# CenterBoard_Mega16.net
KiCad netlist of a schematic drawn in Altium Designer
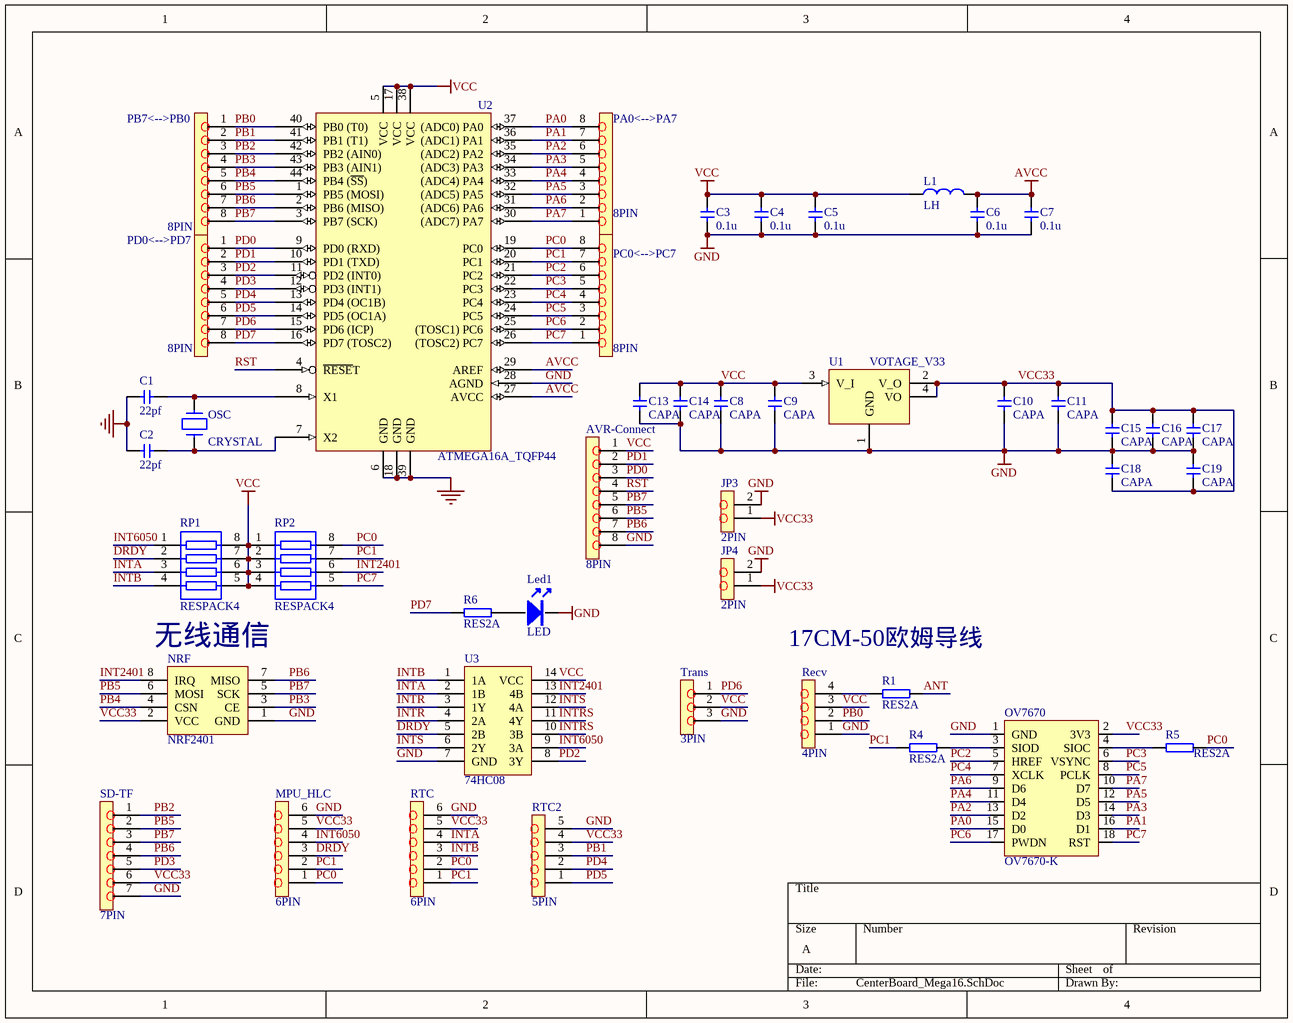
[diagram p0: CenterBoard_Mega16.SchDoc]

(export (version "E")
  (design (tool "Eeschema 10.0.6"))
  (components
    (comp (ref "AVR-Connect") (value "8PIN") (footprint "SIP8") (libsource (lib "") (part "8PIN_1")))
    (comp (ref "C1") (value "22pf") (footprint "RC100") (libsource (lib "Common") (part "CAPA")))
    (comp (ref "C2") (value "22pf") (footprint "RC100") (libsource (lib "Common") (part "CAPA")))
    (comp (ref "C3") (value "0.1u") (footprint "RC100") (libsource (lib "Common") (part "CAPA")))
    (comp (ref "C4") (value "0.1u") (footprint "RC100") (libsource (lib "Common") (part "CAPA")))
    (comp (ref "C5") (value "0.1u") (footprint "RC100") (libsource (lib "Common") (part "CAPA")))
    (comp (ref "C6") (value "0.1u") (footprint "RC100") (libsource (lib "Common") (part "CAPA")))
    (comp (ref "C7") (value "0.1u") (footprint "RC100") (libsource (lib "Common") (part "CAPA")))
    (comp (ref "C8") (value "CAPA") (footprint "RC100") (libsource (lib "Common") (part "CAPA")))
    (comp (ref "C9") (value "CAPA") (footprint "RC100") (libsource (lib "Common") (part "CAPA")))
    (comp (ref "C10") (value "CAPA") (footprint "RC100") (libsource (lib "Common") (part "CAPA")))
    (comp (ref "C11") (value "CAPA") (footprint "RC100") (libsource (lib "Common") (part "CAPA")))
    (comp (ref "C13") (value "CAPA") (footprint "RC100") (libsource (lib "Common") (part "CAPA")))
    (comp (ref "C14") (value "CAPA") (footprint "RC100") (libsource (lib "Common") (part "CAPA")))
    (comp (ref "C15") (value "CAPA") (footprint "RC100") (libsource (lib "Common") (part "CAPA")))
    (comp (ref "C16") (value "CAPA") (footprint "RC100") (libsource (lib "Common") (part "CAPA")))
    (comp (ref "C17") (value "CAPA") (footprint "RC100") (libsource (lib "Common") (part "CAPA")))
    (comp (ref "C18") (value "CAPA") (footprint "RC100") (libsource (lib "Common") (part "CAPA")))
    (comp (ref "C19") (value "CAPA") (footprint "RC100") (libsource (lib "Common") (part "CAPA")))
    (comp (ref "JP3") (value "2PIN") (footprint "SIP2") (libsource (lib "Common") (part "2PIN")))
    (comp (ref "JP4") (value "2PIN") (footprint "SIP2") (libsource (lib "Common") (part "2PIN")))
    (comp (ref "L1") (value "LH") (footprint "1206") (libsource (lib "Common") (part "LH")))
    (comp (ref "Led1") (value "LED") (footprint "LED") (libsource (lib "Common") (part "LED")))
    (comp (ref "MPU_HLC") (value "6PIN") (footprint "SIP6") (libsource (lib "Common") (part "6PIN")))
    (comp (ref "NRF") (value "NRF2401") (footprint "NRF2401") (libsource (lib "Common") (part "NRF2401")))
    (comp (ref "OSC") (value "CRYSTAL") (footprint "OSC200") (libsource (lib "Common") (part "CRYSTAL")))
    (comp (ref "OV7670") (value "OV7670-K") (footprint "SIP9X2") (libsource (lib "Common") (part "OV7670-K")))
    (comp (ref "PA0<-->PA7") (value "8PIN") (footprint "SIP8") (libsource (lib "Common") (part "8PIN")))
    (comp (ref "PB7<-->PB0") (value "8PIN") (footprint "SIP8") (libsource (lib "") (part "8PIN_1")))
    (comp (ref "PC0<-->PC7") (value "8PIN") (footprint "SIP8") (libsource (lib "Common") (part "8PIN")))
    (comp (ref "PD0<-->PD7") (value "8PIN") (footprint "SIP8") (libsource (lib "") (part "8PIN_1")))
    (comp (ref "R1") (value "RES2A") (footprint "0805") (libsource (lib "Common") (part "RES2A")))
    (comp (ref "R4") (value "RES2A") (footprint "0805") (libsource (lib "Common") (part "RES2A")))
    (comp (ref "R5") (value "RES2A") (footprint "0805") (libsource (lib "Common") (part "RES2A")))
    (comp (ref "R6") (value "RES2A") (footprint "0805") (libsource (lib "Common") (part "RES2A")))
    (comp (ref "Recv") (value "4PIN") (footprint "SIP4") (libsource (lib "Common") (part "4PIN")))
    (comp (ref "RP1") (value "RESPACK4") (footprint "RN4") (libsource (lib "Common") (part "RESPACK4")))
    (comp (ref "RP2") (value "RESPACK4") (footprint "RN4") (libsource (lib "Common") (part "RESPACK4")))
    (comp (ref "RTC") (value "6PIN") (footprint "SIP6") (libsource (lib "Common") (part "6PIN")))
    (comp (ref "RTC2") (value "5PIN") (footprint "SIP5") (libsource (lib "Common") (part "5PIN")))
    (comp (ref "SD-TF") (value "7PIN") (footprint "SIP7") (libsource (lib "Common") (part "7PIN")))
    (comp (ref "Trans") (value "3PIN") (footprint "SIP3") (libsource (lib "Common") (part "3PIN")))
    (comp (ref "U1")
      (value "VOTAGE_V33")
      (footprint "SOT-223")
      (libsource (lib "Common") (part "VOTAGE_V33"))
    )
    (comp (ref "U2")
      (value "ATMEGA16A_TQFP44")
      (footprint "TQFP-44")
      (description "Atmel Microcontroller - Library created by carel..  <www.mpfreezone.com>")
      (libsource (lib "MCU") (part "ATMEGA16A_TQFP44"))
    )
    (comp (ref "U3") (value "74HC08") (footprint "SO-14") (libsource (lib "Common") (part "74HC08")))
  )
  (nets
    (net (code "1") (name "/ANT") (class "Default") (node (ref "R1") (pin "2") (pintype "passive")))
    (net (code "2") (name "/DRDY") (class "Default")
      (node (ref "MPU_HLC") (pin "3") (pintype "passive"))
      (node (ref "RP1") (pin "2") (pintype "passive"))
      (node (ref "U3") (pin "5") (pinfunction "2B_5") (pintype "passive"))
    )
    (net (code "3") (name "/INT2401") (class "Default")
      (node (ref "NRF") (pin "8") (pinfunction "IRQ_8") (pintype "passive"))
      (node (ref "RP2") (pin "6") (pintype "passive"))
      (node (ref "U3") (pin "13") (pinfunction "4B_13") (pintype "passive"))
    )
    (net (code "4") (name "/INT6050") (class "Default")
      (node (ref "MPU_HLC") (pin "4") (pintype "passive"))
      (node (ref "RP1") (pin "1") (pintype "passive"))
      (node (ref "U3") (pin "9") (pinfunction "3A_9") (pintype "passive"))
    )
    (net (code "5") (name "/INTA") (class "Default")
      (node (ref "RP1") (pin "3") (pintype "passive"))
      (node (ref "RTC") (pin "4") (pintype "passive"))
      (node (ref "U3") (pin "2") (pinfunction "1B_2") (pintype "passive"))
    )
    (net (code "6") (name "/INTB") (class "Default")
      (node (ref "RP1") (pin "4") (pintype "passive"))
      (node (ref "RTC") (pin "3") (pintype "passive"))
      (node (ref "U3") (pin "1") (pinfunction "1A_1") (pintype "passive"))
    )
    (net (code "7") (name "/INTR") (class "Default")
      (node (ref "U3") (pin "3") (pinfunction "1Y_3") (pintype "passive"))
      (node (ref "U3") (pin "4") (pinfunction "2A_4") (pintype "passive"))
    )
    (net (code "8") (name "/INTRS") (class "Default")
      (node (ref "U3") (pin "10") (pinfunction "3B_10") (pintype "passive"))
      (node (ref "U3") (pin "11") (pinfunction "4Y_11") (pintype "passive"))
    )
    (net (code "9") (name "/INTS") (class "Default")
      (node (ref "U3") (pin "12") (pinfunction "4A_12") (pintype "passive"))
      (node (ref "U3") (pin "6") (pinfunction "2Y_6") (pintype "passive"))
    )
    (net (code "10") (name "/PA0") (class "Default")
      (node (ref "OV7670") (pin "15") (pinfunction "D0_15") (pintype "passive"))
      (node (ref "PA0<-->PA7") (pin "8") (pintype "passive"))
      (node (ref "U2") (pin "37") (pinfunction "(ADC0)_PA0_37") (pintype "bidirectional"))
    )
    (net (code "11") (name "/PA1") (class "Default")
      (node (ref "OV7670") (pin "16") (pinfunction "D1_16") (pintype "passive"))
      (node (ref "PA0<-->PA7") (pin "7") (pintype "passive"))
      (node (ref "U2") (pin "36") (pinfunction "(ADC1)_PA1_36") (pintype "bidirectional"))
    )
    (net (code "12") (name "/PA2") (class "Default")
      (node (ref "OV7670") (pin "13") (pinfunction "D2_13") (pintype "passive"))
      (node (ref "PA0<-->PA7") (pin "6") (pintype "passive"))
      (node (ref "U2") (pin "35") (pinfunction "(ADC2)_PA2_35") (pintype "bidirectional"))
    )
    (net (code "13") (name "/PA3") (class "Default")
      (node (ref "OV7670") (pin "14") (pinfunction "D3_14") (pintype "passive"))
      (node (ref "PA0<-->PA7") (pin "5") (pintype "passive"))
      (node (ref "U2") (pin "34") (pinfunction "(ADC3)_PA3_34") (pintype "bidirectional"))
    )
    (net (code "14") (name "/PA4") (class "Default")
      (node (ref "OV7670") (pin "11") (pinfunction "D4_11") (pintype "passive"))
      (node (ref "PA0<-->PA7") (pin "4") (pintype "passive"))
      (node (ref "U2") (pin "33") (pinfunction "(ADC4)_PA4_33") (pintype "bidirectional"))
    )
    (net (code "15") (name "/PA5") (class "Default")
      (node (ref "OV7670") (pin "12") (pinfunction "D5_12") (pintype "passive"))
      (node (ref "PA0<-->PA7") (pin "3") (pintype "passive"))
      (node (ref "U2") (pin "32") (pinfunction "(ADC5)_PA5_32") (pintype "bidirectional"))
    )
    (net (code "16") (name "/PA6") (class "Default")
      (node (ref "OV7670") (pin "9") (pinfunction "D6_9") (pintype "passive"))
      (node (ref "PA0<-->PA7") (pin "2") (pintype "passive"))
      (node (ref "U2") (pin "31") (pinfunction "(ADC6)_PA6_31") (pintype "bidirectional"))
    )
    (net (code "17") (name "/PA7") (class "Default")
      (node (ref "OV7670") (pin "10") (pinfunction "D7_10") (pintype "passive"))
      (node (ref "PA0<-->PA7") (pin "1") (pintype "passive"))
      (node (ref "U2") (pin "30") (pinfunction "(ADC7)_PA7_30") (pintype "bidirectional"))
    )
    (net (code "18") (name "/PB0") (class "Default")
      (node (ref "PB7<-->PB0") (pin "1") (pintype "passive"))
      (node (ref "Recv") (pin "2") (pintype "passive"))
      (node (ref "U2") (pin "40") (pinfunction "PB0_(T0)_40") (pintype "bidirectional"))
    )
    (net (code "19") (name "/PB1") (class "Default")
      (node (ref "PB7<-->PB0") (pin "2") (pintype "passive"))
      (node (ref "RTC2") (pin "3") (pintype "passive"))
      (node (ref "U2") (pin "41") (pinfunction "PB1_(T1)_41") (pintype "bidirectional"))
    )
    (net (code "20") (name "/PB2") (class "Default")
      (node (ref "PB7<-->PB0") (pin "3") (pintype "passive"))
      (node (ref "SD-TF") (pin "1") (pintype "passive"))
      (node (ref "U2") (pin "42") (pinfunction "PB2_(AIN0)_42") (pintype "bidirectional"))
    )
    (net (code "21") (name "/PB3") (class "Default")
      (node (ref "NRF") (pin "3") (pinfunction "CE_3") (pintype "passive"))
      (node (ref "PB7<-->PB0") (pin "4") (pintype "passive"))
      (node (ref "U2") (pin "43") (pinfunction "PB3_(AIN1)_43") (pintype "bidirectional"))
    )
    (net (code "22") (name "/PB4") (class "Default")
      (node (ref "NRF") (pin "4") (pinfunction "CSN_4") (pintype "passive"))
      (node (ref "PB7<-->PB0") (pin "5") (pintype "passive"))
      (node (ref "U2") (pin "44") (pinfunction "PB4_(~{SS})_44") (pintype "bidirectional"))
    )
    (net (code "23") (name "/PB5") (class "Default")
      (node (ref "AVR-Connect") (pin "6") (pintype "passive"))
      (node (ref "NRF") (pin "6") (pinfunction "MOSI_6") (pintype "passive"))
      (node (ref "PB7<-->PB0") (pin "6") (pintype "passive"))
      (node (ref "SD-TF") (pin "2") (pintype "passive"))
      (node (ref "U2") (pin "1") (pinfunction "PB5_(MOSI)_1") (pintype "bidirectional"))
    )
    (net (code "24") (name "/PB6") (class "Default")
      (node (ref "AVR-Connect") (pin "7") (pintype "passive"))
      (node (ref "NRF") (pin "7") (pinfunction "MISO_7") (pintype "passive"))
      (node (ref "PB7<-->PB0") (pin "7") (pintype "passive"))
      (node (ref "SD-TF") (pin "4") (pintype "passive"))
      (node (ref "U2") (pin "2") (pinfunction "PB6_(MISO)_2") (pintype "bidirectional"))
    )
    (net (code "25") (name "/PB7") (class "Default")
      (node (ref "AVR-Connect") (pin "5") (pintype "passive"))
      (node (ref "NRF") (pin "5") (pinfunction "SCK_5") (pintype "passive"))
      (node (ref "PB7<-->PB0") (pin "8") (pintype "passive"))
      (node (ref "SD-TF") (pin "3") (pintype "passive"))
      (node (ref "U2") (pin "3") (pinfunction "PB7_(SCK)_3") (pintype "bidirectional"))
    )
    (net (code "26") (name "/PC0") (class "Default")
      (node (ref "MPU_HLC") (pin "1") (pintype "passive"))
      (node (ref "PC0<-->PC7") (pin "8") (pintype "passive"))
      (node (ref "R5") (pin "2") (pintype "passive"))
      (node (ref "RP2") (pin "8") (pintype "passive"))
      (node (ref "RTC") (pin "2") (pintype "passive"))
      (node (ref "U2") (pin "19") (pinfunction "PC0_19") (pintype "bidirectional"))
    )
    (net (code "27") (name "/PC1") (class "Default")
      (node (ref "MPU_HLC") (pin "2") (pintype "passive"))
      (node (ref "PC0<-->PC7") (pin "7") (pintype "passive"))
      (node (ref "R4") (pin "1") (pintype "passive"))
      (node (ref "RP2") (pin "7") (pintype "passive"))
      (node (ref "RTC") (pin "1") (pintype "passive"))
      (node (ref "U2") (pin "20") (pinfunction "PC1_20") (pintype "bidirectional"))
    )
    (net (code "28") (name "/PC2") (class "Default")
      (node (ref "OV7670") (pin "5") (pinfunction "HREF_5") (pintype "passive"))
      (node (ref "PC0<-->PC7") (pin "6") (pintype "passive"))
      (node (ref "U2") (pin "21") (pinfunction "PC2_21") (pintype "bidirectional"))
    )
    (net (code "29") (name "/PC3") (class "Default")
      (node (ref "OV7670") (pin "6") (pinfunction "VSYNC_6") (pintype "passive"))
      (node (ref "PC0<-->PC7") (pin "5") (pintype "passive"))
      (node (ref "U2") (pin "22") (pinfunction "PC3_22") (pintype "bidirectional"))
    )
    (net (code "30") (name "/PC4") (class "Default")
      (node (ref "OV7670") (pin "7") (pinfunction "XCLK_7") (pintype "passive"))
      (node (ref "PC0<-->PC7") (pin "4") (pintype "passive"))
      (node (ref "U2") (pin "23") (pinfunction "PC4_23") (pintype "bidirectional"))
    )
    (net (code "31") (name "/PC5") (class "Default")
      (node (ref "OV7670") (pin "8") (pinfunction "PCLK_8") (pintype "passive"))
      (node (ref "PC0<-->PC7") (pin "3") (pintype "passive"))
      (node (ref "U2") (pin "24") (pinfunction "PC5_24") (pintype "bidirectional"))
    )
    (net (code "32") (name "/PC6") (class "Default")
      (node (ref "OV7670") (pin "17") (pinfunction "PWDN_17") (pintype "passive"))
      (node (ref "PC0<-->PC7") (pin "2") (pintype "passive"))
      (node (ref "U2") (pin "25") (pinfunction "(TOSC1)_PC6_25") (pintype "bidirectional"))
    )
    (net (code "33") (name "/PC7") (class "Default")
      (node (ref "OV7670") (pin "18") (pinfunction "RST_18") (pintype "passive"))
      (node (ref "PC0<-->PC7") (pin "1") (pintype "passive"))
      (node (ref "RP2") (pin "5") (pintype "passive"))
      (node (ref "U2") (pin "26") (pinfunction "(TOSC2)_PC7_26") (pintype "bidirectional"))
    )
    (net (code "34") (name "/PD0") (class "Default")
      (node (ref "AVR-Connect") (pin "3") (pintype "passive"))
      (node (ref "PD0<-->PD7") (pin "1") (pintype "passive"))
      (node (ref "U2") (pin "9") (pinfunction "PD0_(RXD)_9") (pintype "bidirectional"))
    )
    (net (code "35") (name "/PD1") (class "Default")
      (node (ref "AVR-Connect") (pin "2") (pintype "passive"))
      (node (ref "PD0<-->PD7") (pin "2") (pintype "passive"))
      (node (ref "U2") (pin "10") (pinfunction "PD1_(TXD)_10") (pintype "bidirectional"))
    )
    (net (code "36") (name "/PD2") (class "Default")
      (node (ref "PD0<-->PD7") (pin "3") (pintype "passive"))
      (node (ref "U2") (pin "11") (pinfunction "PD2_(INT0)_11") (pintype "bidirectional"))
      (node (ref "U3") (pin "8") (pinfunction "3Y_8") (pintype "passive"))
    )
    (net (code "37") (name "/PD3") (class "Default")
      (node (ref "PD0<-->PD7") (pin "4") (pintype "passive"))
      (node (ref "SD-TF") (pin "5") (pintype "passive"))
      (node (ref "U2") (pin "12") (pinfunction "PD3_(INT1)_12") (pintype "bidirectional"))
    )
    (net (code "38") (name "/PD4") (class "Default")
      (node (ref "PD0<-->PD7") (pin "5") (pintype "passive"))
      (node (ref "RTC2") (pin "2") (pintype "passive"))
      (node (ref "U2") (pin "13") (pinfunction "PD4_(OC1B)_13") (pintype "bidirectional"))
    )
    (net (code "39") (name "/PD5") (class "Default")
      (node (ref "PD0<-->PD7") (pin "6") (pintype "passive"))
      (node (ref "RTC2") (pin "1") (pintype "passive"))
      (node (ref "U2") (pin "14") (pinfunction "PD5_(OC1A)_14") (pintype "bidirectional"))
    )
    (net (code "40") (name "/PD6") (class "Default")
      (node (ref "PD0<-->PD7") (pin "7") (pintype "passive"))
      (node (ref "Trans") (pin "1") (pintype "passive"))
      (node (ref "U2") (pin "15") (pinfunction "PD6_(ICP)_15") (pintype "bidirectional"))
    )
    (net (code "41") (name "/PD7") (class "Default")
      (node (ref "PD0<-->PD7") (pin "8") (pintype "passive"))
      (node (ref "R6") (pin "1") (pintype "passive"))
      (node (ref "U2") (pin "16") (pinfunction "PD7_(TOSC2)_16") (pintype "bidirectional"))
    )
    (net (code "42") (name "/RST") (class "Default")
      (node (ref "AVR-Connect") (pin "4") (pintype "passive"))
      (node (ref "U2") (pin "4") (pinfunction "~{RESE}T_4") (pintype "input"))
    )
    (net (code "43") (name "AVCC") (class "Default")
      (node (ref "C6") (pin "1") (pintype "passive"))
      (node (ref "C7") (pin "1") (pintype "passive"))
      (node (ref "L1") (pin "2") (pintype "passive"))
      (node (ref "U2") (pin "27") (pinfunction "AVCC_27") (pintype "bidirectional"))
      (node (ref "U2") (pin "29") (pinfunction "AREF_29") (pintype "bidirectional"))
    )
    (net (code "44") (name "GND") (class "Default")
      (node (ref "AVR-Connect") (pin "8") (pintype "passive"))
      (node (ref "C1") (pin "1") (pintype "passive"))
      (node (ref "C10") (pin "2") (pintype "passive"))
      (node (ref "C11") (pin "2") (pintype "passive"))
      (node (ref "C13") (pin "2") (pintype "passive"))
      (node (ref "C14") (pin "2") (pintype "passive"))
      (node (ref "C15") (pin "2") (pintype "passive"))
      (node (ref "C16") (pin "2") (pintype "passive"))
      (node (ref "C17") (pin "2") (pintype "passive"))
      (node (ref "C18") (pin "1") (pintype "passive"))
      (node (ref "C19") (pin "1") (pintype "passive"))
      (node (ref "C2") (pin "1") (pintype "passive"))
      (node (ref "C3") (pin "2") (pintype "passive"))
      (node (ref "C4") (pin "2") (pintype "passive"))
      (node (ref "C5") (pin "2") (pintype "passive"))
      (node (ref "C6") (pin "2") (pintype "passive"))
      (node (ref "C7") (pin "2") (pintype "passive"))
      (node (ref "C8") (pin "2") (pintype "passive"))
      (node (ref "C9") (pin "2") (pintype "passive"))
      (node (ref "JP3") (pin "2") (pintype "passive"))
      (node (ref "JP4") (pin "2") (pintype "passive"))
      (node (ref "Led1") (pin "K") (pintype "passive"))
      (node (ref "MPU_HLC") (pin "6") (pintype "passive"))
      (node (ref "NRF") (pin "1") (pinfunction "GND_1") (pintype "passive"))
      (node (ref "OV7670") (pin "1") (pinfunction "GND_1") (pintype "passive"))
      (node (ref "RTC") (pin "6") (pintype "passive"))
      (node (ref "RTC2") (pin "5") (pintype "passive"))
      (node (ref "Recv") (pin "1") (pintype "passive"))
      (node (ref "SD-TF") (pin "7") (pintype "passive"))
      (node (ref "Trans") (pin "3") (pintype "passive"))
      (node (ref "U1") (pin "1") (pinfunction "GND_1") (pintype "power_in"))
      (node (ref "U2") (pin "18") (pinfunction "GND_18") (pintype "passive"))
      (node (ref "U2") (pin "28") (pinfunction "AGND_28") (pintype "input"))
      (node (ref "U2") (pin "39") (pinfunction "GND_39") (pintype "power_in"))
      (node (ref "U2") (pin "6") (pinfunction "GND_6") (pintype "passive"))
      (node (ref "U3") (pin "7") (pinfunction "GND_7") (pintype "passive"))
    )
    (net (code "45") (name "Net-(Led1-PadA)") (class "Default")
      (node (ref "Led1") (pin "A") (pintype "passive"))
      (node (ref "R6") (pin "2") (pintype "passive"))
    )
    (net (code "46") (name "Net-(OV7670-SIOC)") (class "Default")
      (node (ref "OV7670") (pin "4") (pinfunction "SIOC_4") (pintype "passive"))
      (node (ref "R5") (pin "1") (pintype "passive"))
    )
    (net (code "47") (name "Net-(OV7670-SIOD)") (class "Default")
      (node (ref "OV7670") (pin "3") (pinfunction "SIOD_3") (pintype "passive"))
      (node (ref "R4") (pin "2") (pintype "passive"))
    )
    (net (code "48") (name "Net-(R1-Pad1)") (class "Default")
      (node (ref "R1") (pin "1") (pintype "passive"))
      (node (ref "Recv") (pin "4") (pintype "passive"))
    )
    (net (code "49") (name "Net-(U2-X1)") (class "Default")
      (node (ref "C1") (pin "2") (pintype "passive"))
      (node (ref "OSC") (pin "2") (pintype "passive"))
      (node (ref "U2") (pin "8") (pinfunction "X1_8") (pintype "input"))
    )
    (net (code "50") (name "Net-(U2-X2)") (class "Default")
      (node (ref "C2") (pin "2") (pintype "passive"))
      (node (ref "OSC") (pin "1") (pintype "passive"))
      (node (ref "U2") (pin "7") (pinfunction "X2_7") (pintype "input"))
    )
    (net (code "51") (name "VCC") (class "Default")
      (node (ref "AVR-Connect") (pin "1") (pintype "passive"))
      (node (ref "C13") (pin "1") (pintype "passive"))
      (node (ref "C14") (pin "1") (pintype "passive"))
      (node (ref "C3") (pin "1") (pintype "passive"))
      (node (ref "C4") (pin "1") (pintype "passive"))
      (node (ref "C5") (pin "1") (pintype "passive"))
      (node (ref "C8") (pin "1") (pintype "passive"))
      (node (ref "C9") (pin "1") (pintype "passive"))
      (node (ref "L1") (pin "1") (pintype "passive"))
      (node (ref "RP1") (pin "5") (pintype "passive"))
      (node (ref "RP1") (pin "6") (pintype "passive"))
      (node (ref "RP1") (pin "7") (pintype "passive"))
      (node (ref "RP1") (pin "8") (pintype "passive"))
      (node (ref "RP2") (pin "1") (pintype "passive"))
      (node (ref "RP2") (pin "2") (pintype "passive"))
      (node (ref "RP2") (pin "3") (pintype "passive"))
      (node (ref "RP2") (pin "4") (pintype "passive"))
      (node (ref "Recv") (pin "3") (pintype "passive"))
      (node (ref "Trans") (pin "2") (pintype "passive"))
      (node (ref "U1") (pin "3") (pinfunction "V_I_3") (pintype "input"))
      (node (ref "U2") (pin "17") (pinfunction "VCC_17") (pintype "passive"))
      (node (ref "U2") (pin "38") (pinfunction "VCC_38") (pintype "power_in"))
      (node (ref "U2") (pin "5") (pinfunction "VCC_5") (pintype "passive"))
      (node (ref "U3") (pin "14") (pinfunction "VCC_14") (pintype "passive"))
    )
    (net (code "52") (name "VCC33") (class "Default")
      (node (ref "C10") (pin "1") (pintype "passive"))
      (node (ref "C11") (pin "1") (pintype "passive"))
      (node (ref "C15") (pin "1") (pintype "passive"))
      (node (ref "C16") (pin "1") (pintype "passive"))
      (node (ref "C17") (pin "1") (pintype "passive"))
      (node (ref "C18") (pin "2") (pintype "passive"))
      (node (ref "C19") (pin "2") (pintype "passive"))
      (node (ref "JP3") (pin "1") (pintype "passive"))
      (node (ref "JP4") (pin "1") (pintype "passive"))
      (node (ref "MPU_HLC") (pin "5") (pintype "passive"))
      (node (ref "NRF") (pin "2") (pinfunction "VCC_2") (pintype "passive"))
      (node (ref "OV7670") (pin "2") (pinfunction "3V3_2") (pintype "passive"))
      (node (ref "RTC") (pin "5") (pintype "passive"))
      (node (ref "RTC2") (pin "4") (pintype "passive"))
      (node (ref "SD-TF") (pin "6") (pintype "passive"))
      (node (ref "U1") (pin "2") (pinfunction "V_O_2") (pintype "power_in"))
      (node (ref "U1") (pin "4") (pinfunction "VO_4") (pintype "passive"))
    )
  )
)
